# AST1020.net
KiCad netlist of a schematic drawn in EAGLE
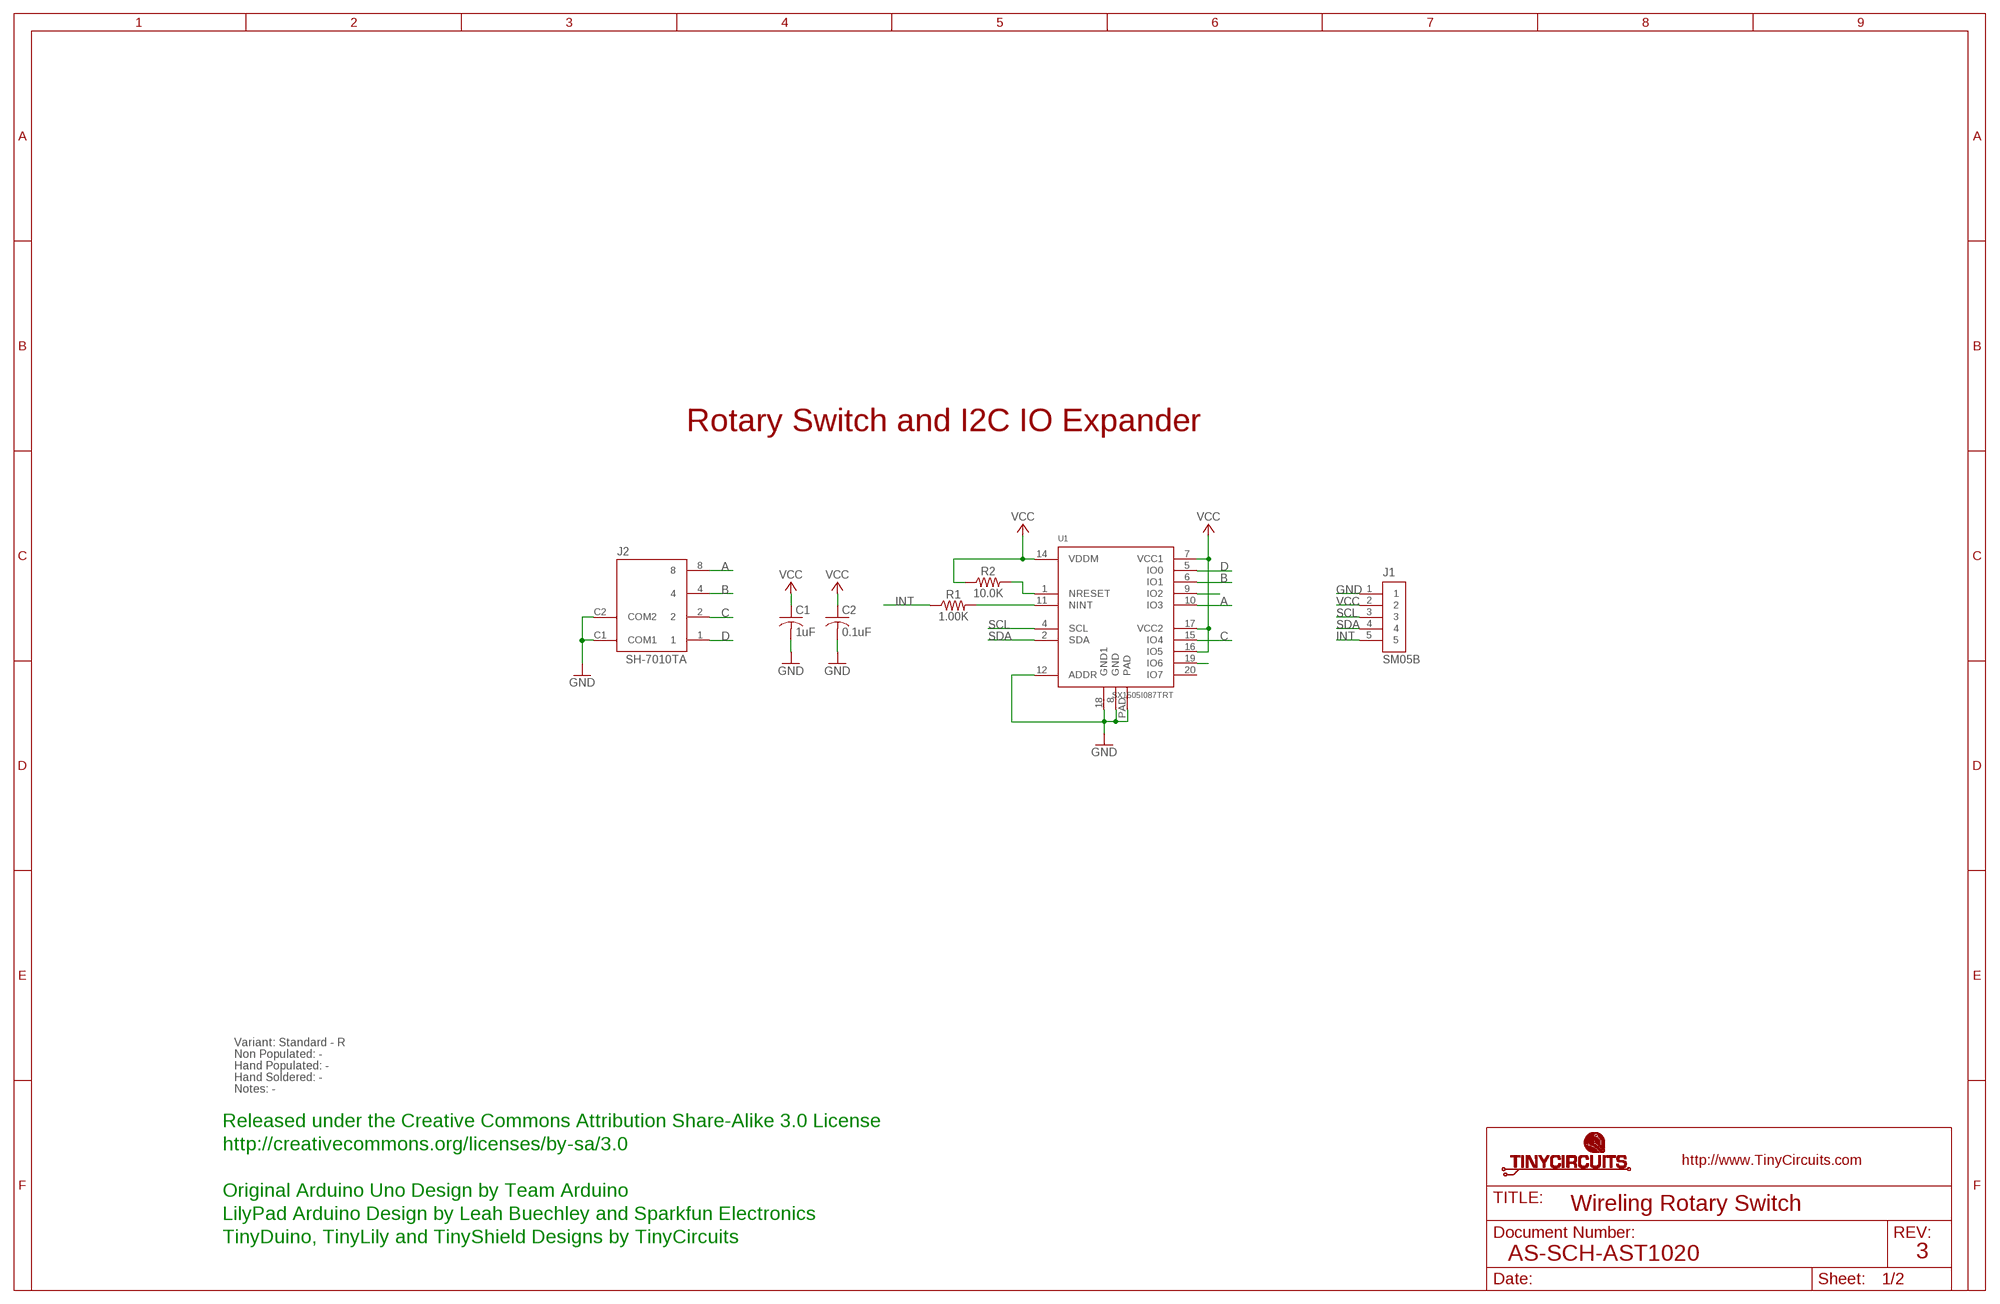
[diagram p0: schematic, sheet 1]
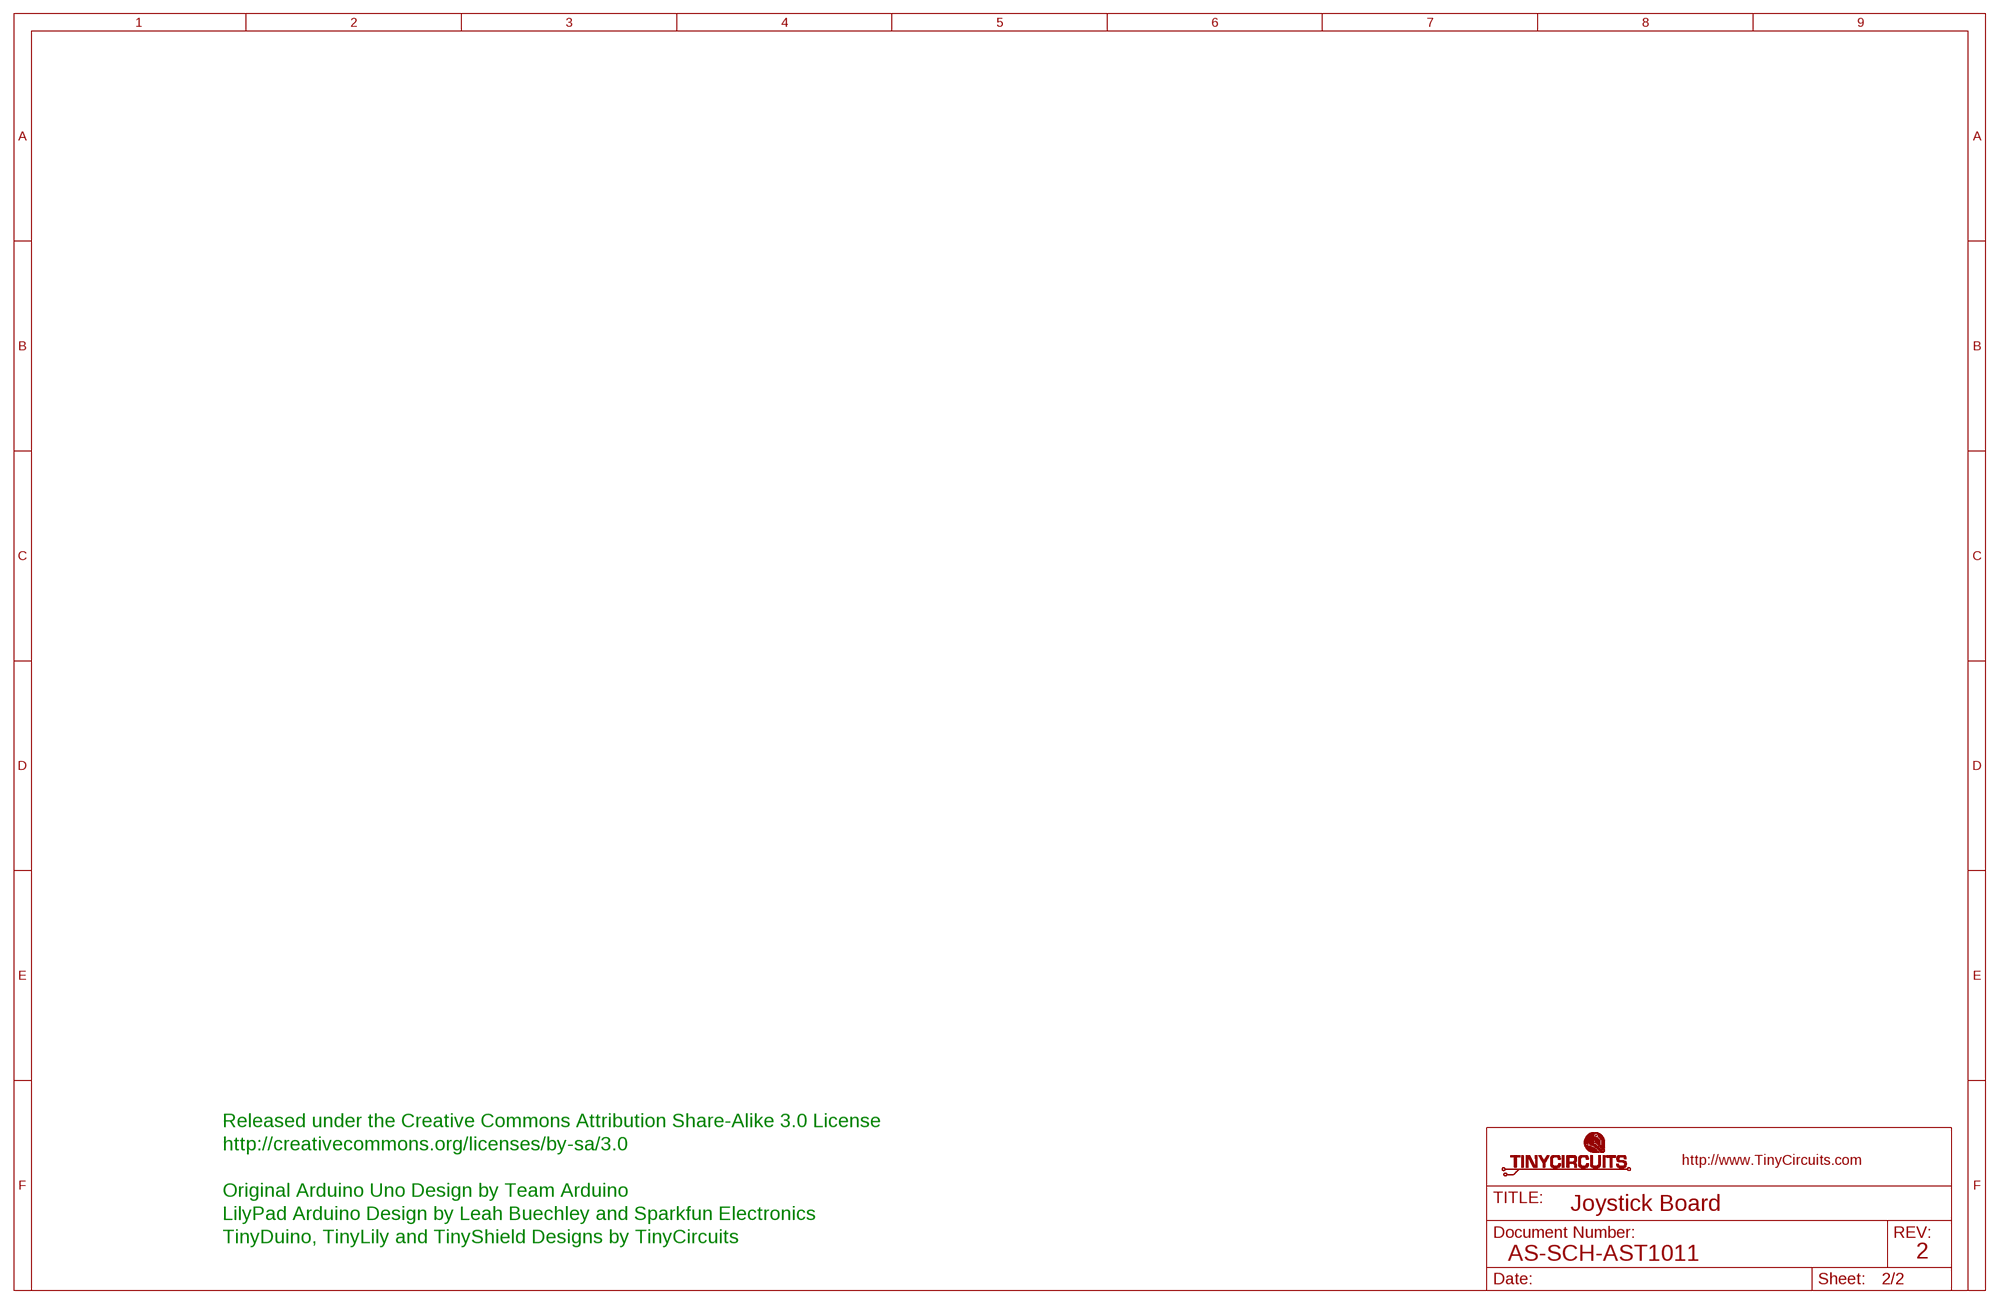
[diagram p1: schematic, sheet 2]

(export (version "E")
  (design (tool "Eeschema 10.0.6"))
  (components
    (comp (ref "C1")
      (value "1uF")
      (footprint "eagle-import:C0402")
      (fields (field (name "PARTNO") "AS-ITM-00105") (field (name "PARTNO_1") "AS-ITM-00105"))
      (libsource (lib "eagle-import") (part "AS-ITM-00105"))
    )
    (comp (ref "C2")
      (value "0.1uF")
      (footprint "eagle-import:C0402")
      (fields (field (name "PARTNO") "AS-ITM-00008"))
      (libsource (lib "eagle-import") (part "AS-ITM-00008"))
    )
    (comp (ref "J1")
      (value "SM05B")
      (footprint "eagle-import:JST_SH_5X1_EDGE")
      (fields (field (name "PARTNO") "AS-ITM-00340"))
      (libsource (lib "eagle-import") (part "AS-ITM-00340EDGE"))
    )
    (comp (ref "J2")
      (value "SH-7010TA")
      (footprint "eagle-import:SH-7000")
      (fields (field (name "PARTNO") "AS-ITM-00295"))
      (libsource (lib "eagle-import") (part "AS-ITM-00295"))
    )
    (comp (ref "R1")
      (value "1.00K")
      (footprint "eagle-import:0402")
      (fields (field (name "PARTNO") "AS-ITM-00003"))
      (libsource (lib "eagle-import") (part "AS-ITM-00003"))
    )
    (comp (ref "R2")
      (value "10.0K")
      (footprint "eagle-import:0402")
      (fields (field (name "PARTNO") "AS-ITM-00032"))
      (libsource (lib "eagle-import") (part "AS-ITM-00032"))
    )
    (comp (ref "U1")
      (value "SX1505I087TRT")
      (footprint "eagle-import:QFN-UT20")
      (fields (field (name "PARTNO") "AS-ITM-00203"))
      (libsource (lib "eagle-import") (part "AS-ITM-00203"))
    )
  )
  (nets
    (net (code "1") (name "A") (class "Default")
      (node (ref "J2") (pin "8") (pinfunction "8_8") (pintype "bidirectional"))
      (node (ref "U1") (pin "10") (pinfunction "IO3_10") (pintype "bidirectional"))
    )
    (net (code "2") (name "B") (class "Default")
      (node (ref "J2") (pin "4") (pinfunction "4_4") (pintype "bidirectional"))
      (node (ref "U1") (pin "6") (pinfunction "IO1_6") (pintype "bidirectional"))
    )
    (net (code "3") (name "C") (class "Default")
      (node (ref "J2") (pin "2") (pinfunction "2_2") (pintype "bidirectional"))
      (node (ref "U1") (pin "15") (pinfunction "IO4_15") (pintype "bidirectional"))
    )
    (net (code "4") (name "D") (class "Default")
      (node (ref "J2") (pin "1") (pinfunction "1_1") (pintype "bidirectional"))
      (node (ref "U1") (pin "5") (pinfunction "IO0_5") (pintype "bidirectional"))
    )
    (net (code "5") (name "GND") (class "Default")
      (node (ref "C1") (pin "2") (pinfunction "2_2") (pintype "passive"))
      (node (ref "C2") (pin "2") (pinfunction "2_2") (pintype "passive"))
      (node (ref "J1") (pin "1") (pinfunction "1_1") (pintype "bidirectional"))
      (node (ref "J2") (pin "C1") (pinfunction "COM1_C1") (pintype "bidirectional"))
      (node (ref "J2") (pin "C2") (pinfunction "COM2_C2") (pintype "bidirectional"))
      (node (ref "U1") (pin "12") (pinfunction "ADDR_12") (pintype "bidirectional"))
      (node (ref "U1") (pin "18") (pinfunction "GND1_18") (pintype "bidirectional"))
      (node (ref "U1") (pin "8") (pinfunction "GND_8") (pintype "bidirectional"))
      (node (ref "U1") (pin "PAD") (pinfunction "PAD_PAD") (pintype "bidirectional"))
    )
    (net (code "6") (name "INT") (class "Default")
      (node (ref "J1") (pin "5") (pinfunction "5_5") (pintype "bidirectional"))
      (node (ref "R1") (pin "1") (pinfunction "1_1") (pintype "passive"))
    )
    (net (code "7") (name "Net-(U1-NINT)") (class "Default")
      (node (ref "R1") (pin "2") (pinfunction "2_2") (pintype "passive"))
      (node (ref "U1") (pin "11") (pinfunction "NINT_11") (pintype "bidirectional"))
    )
    (net (code "8") (name "Net-(U1-NRESET)") (class "Default")
      (node (ref "R2") (pin "2") (pinfunction "2_2") (pintype "passive"))
      (node (ref "U1") (pin "1") (pinfunction "NRESET_1") (pintype "bidirectional"))
    )
    (net (code "9") (name "SCL") (class "Default")
      (node (ref "J1") (pin "3") (pinfunction "3_3") (pintype "bidirectional"))
      (node (ref "U1") (pin "4") (pinfunction "SCL_4") (pintype "bidirectional"))
    )
    (net (code "10") (name "SDA") (class "Default")
      (node (ref "J1") (pin "4") (pinfunction "4_4") (pintype "bidirectional"))
      (node (ref "U1") (pin "2") (pinfunction "SDA_2") (pintype "bidirectional"))
    )
    (net (code "11") (name "VCC") (class "Default")
      (node (ref "C1") (pin "1") (pinfunction "1_1") (pintype "passive"))
      (node (ref "C2") (pin "1") (pinfunction "1_1") (pintype "passive"))
      (node (ref "J1") (pin "2") (pinfunction "2_2") (pintype "bidirectional"))
      (node (ref "R2") (pin "1") (pinfunction "1_1") (pintype "passive"))
      (node (ref "U1") (pin "14") (pinfunction "VDDM_14") (pintype "bidirectional"))
      (node (ref "U1") (pin "16") (pinfunction "IO5_16") (pintype "bidirectional"))
      (node (ref "U1") (pin "17") (pinfunction "VCC2_17") (pintype "bidirectional"))
      (node (ref "U1") (pin "7") (pinfunction "VCC1_7") (pintype "bidirectional"))
    )
    (net (code "12") (name "unconnected-(U1-IO2-Pad9)") (class "Default")
      (node (ref "U1") (pin "9") (pinfunction "IO2_9") (pintype "bidirectional"))
    )
    (net (code "13") (name "unconnected-(U1-IO6-Pad19)") (class "Default")
      (node (ref "U1") (pin "19") (pinfunction "IO6_19") (pintype "bidirectional"))
    )
    (net (code "14") (name "unconnected-(U1-IO7-Pad20)") (class "Default")
      (node (ref "U1") (pin "20") (pinfunction "IO7_20") (pintype "bidirectional"))
    )
  )
)
